# AstableVibrator.net
KiCad netlist of a schematic drawn in EAGLE
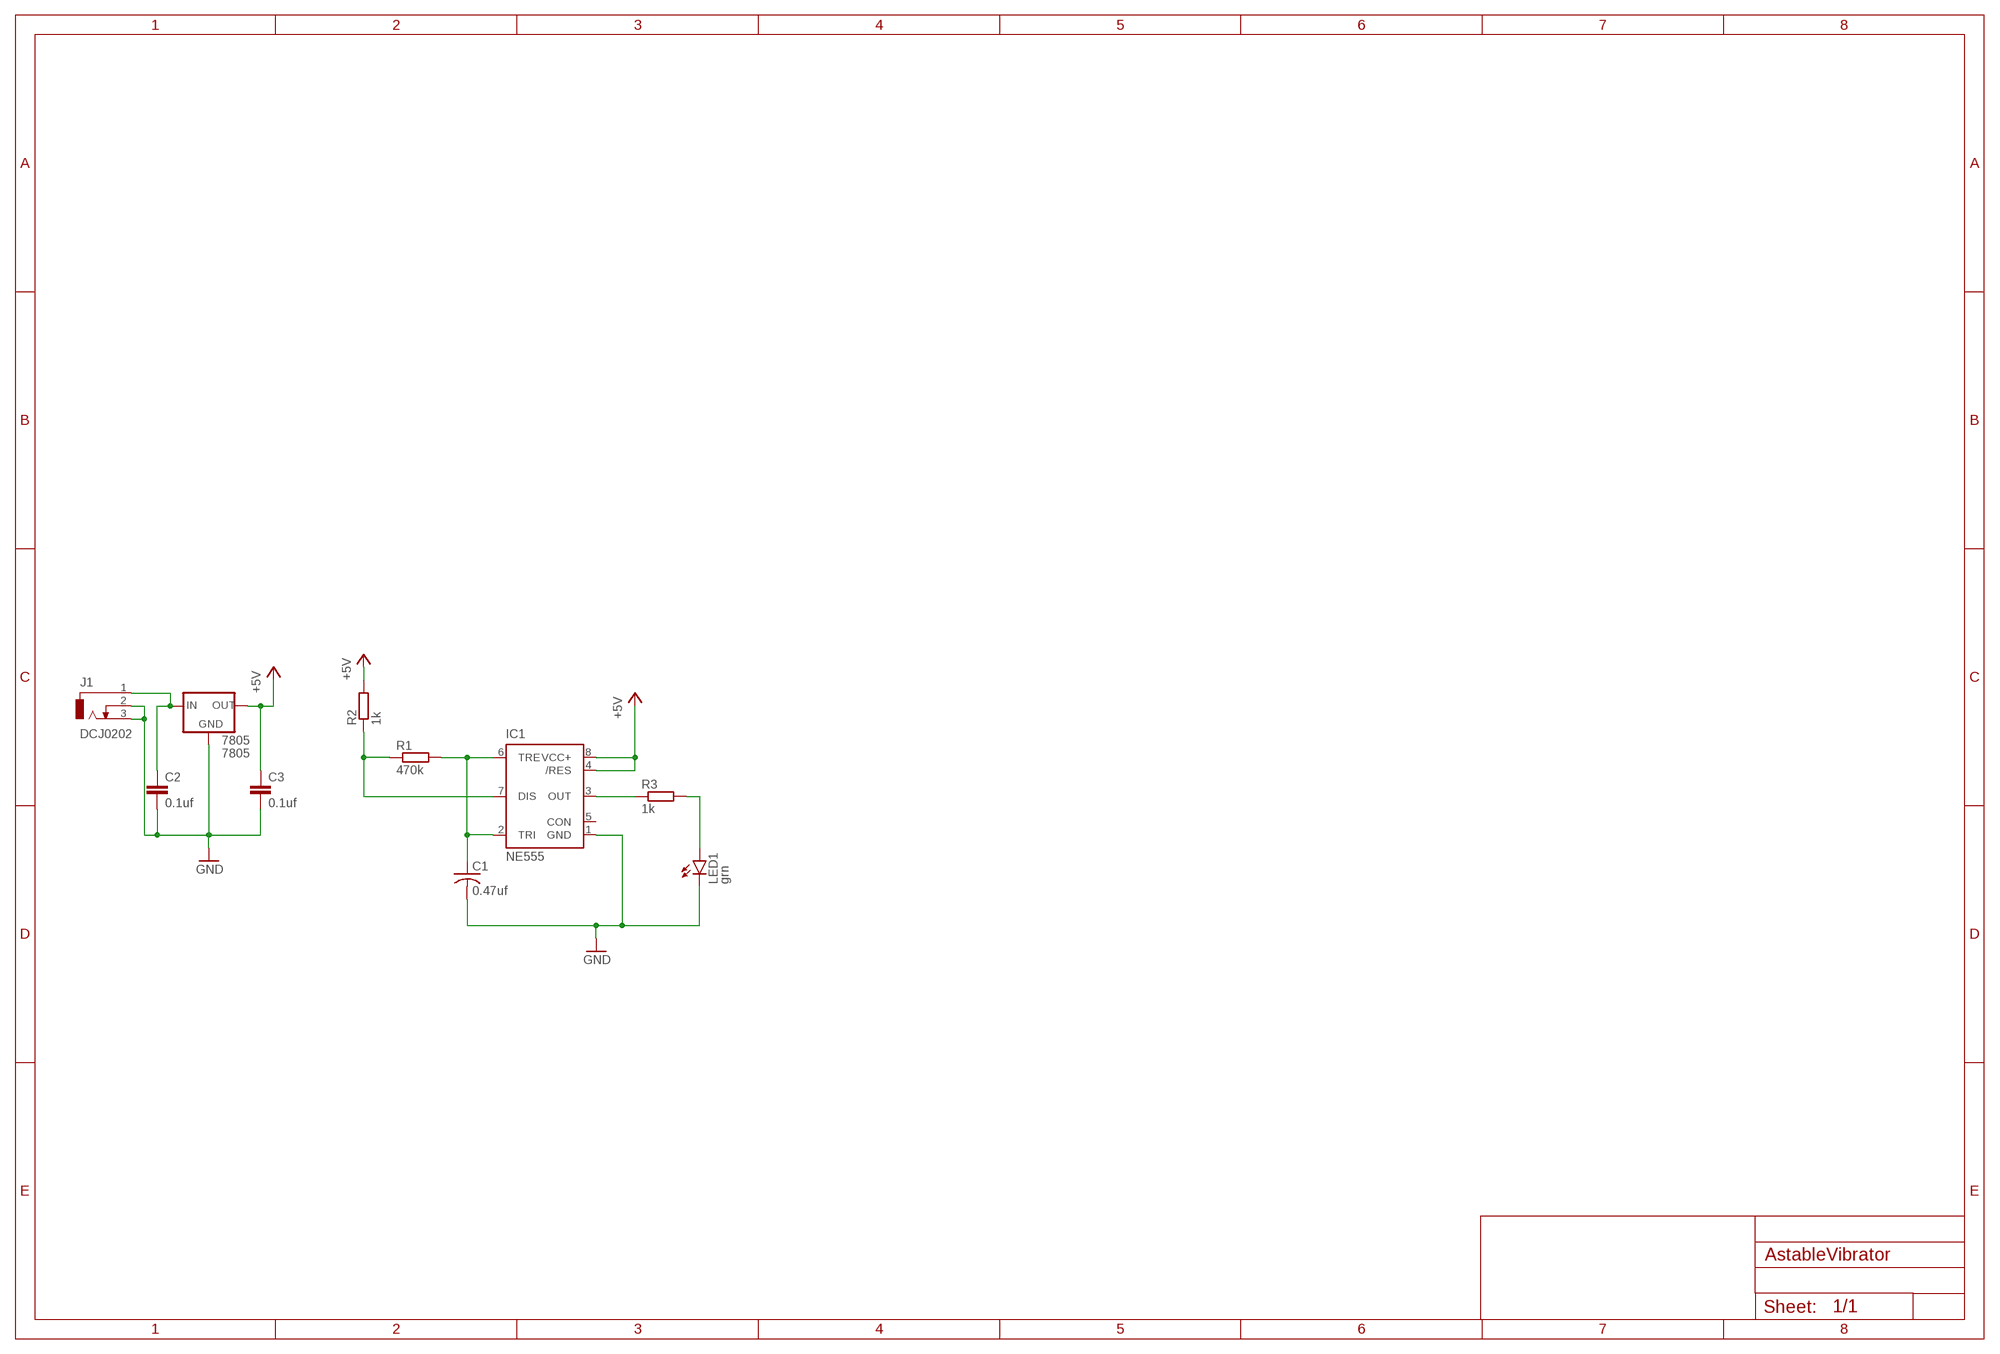
[diagram p0: schematic, sheet 1]

(export (version "E")
  (design (tool "Eeschema 10.0.6"))
  (components
    (comp (ref "7805")
      (value "7805")
      (footprint "eagle-import:78MXXS")
      (libsource (lib "eagle-import") (part "78MXXS"))
    )
    (comp (ref "C1")
      (value "0.47uf")
      (footprint "eagle-import:C025_050-045X075")
      (libsource (lib "eagle-import") (part "C-US025_050-045X075"))
    )
    (comp (ref "C2")
      (value "0.1uf")
      (footprint "eagle-import:C025-050X050")
      (libsource (lib "eagle-import") (part "C-EU025-050X050"))
    )
    (comp (ref "C3")
      (value "0.1uf")
      (footprint "eagle-import:C025-050X050")
      (libsource (lib "eagle-import") (part "C-EU025-050X050"))
    )
    (comp (ref "IC1")
      (value "NE555")
      (footprint "eagle-import:DIL-08")
      (fields (field (name "MF") "Arrow Electronics") (field (name "MPN") "NE555N"))
      (libsource (lib "eagle-import") (part "NE555"))
    )
    (comp (ref "J1")
      (value "DCJ0202")
      (footprint "eagle-import:DCJ0202")
      (libsource (lib "eagle-import") (part "DCJ0202"))
    )
    (comp (ref "LED1")
      (value "grn")
      (footprint "eagle-import:LED5MM")
      (libsource (lib "eagle-import") (part "LED5MM"))
    )
    (comp (ref "R1")
      (value "470k")
      (footprint "eagle-import:0411_15")
      (libsource (lib "eagle-import") (part "R-EU_0411/15"))
    )
    (comp (ref "R2")
      (value "1k")
      (footprint "eagle-import:0411_15")
      (libsource (lib "eagle-import") (part "R-EU_0411/15"))
    )
    (comp (ref "R3")
      (value "1k")
      (footprint "eagle-import:0411_15")
      (libsource (lib "eagle-import") (part "R-EU_0411/15"))
    )
  )
  (nets
    (net (code "1") (name "+5V") (class "Default")
      (node (ref "7805") (pin "OUT") (pinfunction "OUT_OUT") (pintype "passive"))
      (node (ref "C3") (pin "1") (pinfunction "1_1") (pintype "passive"))
      (node (ref "IC1") (pin "4") (pinfunction "/RES_4") (pintype "input"))
      (node (ref "IC1") (pin "8") (pinfunction "VCC+_8") (pintype "power_in"))
      (node (ref "R2") (pin "2") (pinfunction "2_2") (pintype "passive"))
    )
    (net (code "2") (name "GND") (class "Default")
      (node (ref "7805") (pin "GND") (pinfunction "GND_GND") (pintype "input"))
      (node (ref "C1") (pin "2") (pinfunction "2_2") (pintype "passive"))
      (node (ref "C2") (pin "2") (pinfunction "2_2") (pintype "passive"))
      (node (ref "C3") (pin "2") (pinfunction "2_2") (pintype "passive"))
      (node (ref "IC1") (pin "1") (pinfunction "GND_1") (pintype "power_in"))
      (node (ref "J1") (pin "2") (pinfunction "2_2") (pintype "passive"))
      (node (ref "J1") (pin "3") (pinfunction "3_3") (pintype "passive"))
      (node (ref "LED1") (pin "K") (pinfunction "C_K") (pintype "passive"))
    )
    (net (code "3") (name "Net-(7805-PadIN)") (class "Default")
      (node (ref "7805") (pin "IN") (pinfunction "IN_IN") (pintype "input"))
      (node (ref "C2") (pin "1") (pinfunction "1_1") (pintype "passive"))
      (node (ref "J1") (pin "1") (pinfunction "1_1") (pintype "passive"))
    )
    (net (code "4") (name "Net-(IC1-DIS)") (class "Default")
      (node (ref "IC1") (pin "7") (pinfunction "DIS_7") (pintype "input"))
      (node (ref "R1") (pin "1") (pinfunction "1_1") (pintype "passive"))
      (node (ref "R2") (pin "1") (pinfunction "1_1") (pintype "passive"))
    )
    (net (code "5") (name "Net-(IC1-OUT)") (class "Default")
      (node (ref "IC1") (pin "3") (pinfunction "OUT_3") (pintype "output"))
      (node (ref "R3") (pin "1") (pinfunction "1_1") (pintype "passive"))
    )
    (net (code "6") (name "Net-(IC1-TRE)") (class "Default")
      (node (ref "C1") (pin "1") (pinfunction "1_1") (pintype "passive"))
      (node (ref "IC1") (pin "2") (pinfunction "TRI_2") (pintype "input"))
      (node (ref "IC1") (pin "6") (pinfunction "TRE_6") (pintype "input"))
      (node (ref "R1") (pin "2") (pinfunction "2_2") (pintype "passive"))
    )
    (net (code "7") (name "Net-(LED1-PadA)") (class "Default")
      (node (ref "LED1") (pin "A") (pinfunction "A_A") (pintype "passive"))
      (node (ref "R3") (pin "2") (pinfunction "2_2") (pintype "passive"))
    )
    (net (code "8") (name "unconnected-(IC1-CON-Pad5)") (class "Default")
      (node (ref "IC1") (pin "5") (pinfunction "CON_5") (pintype "input"))
    )
  )
)
